# 05_Button.net
KiCad netlist of a schematic drawn in Altium Designer
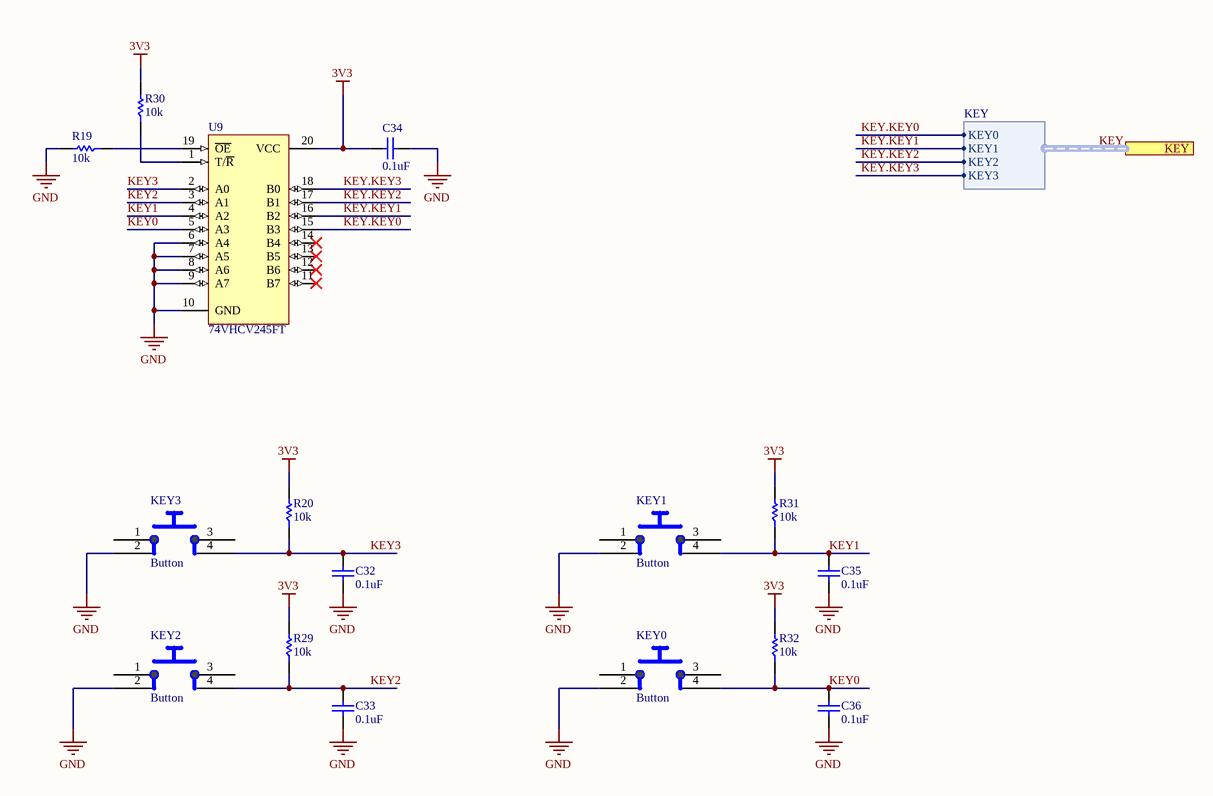
[diagram p0: 05_Button.SchDoc]

(export (version "E")
  (design (tool "Eeschema 10.0.6"))
  (components
    (comp (ref "C32")
      (value "0.1uF")
      (footprint "CAP0603R")
      (description "Capacitor")
      (libsource (lib "Quatro_SchLib") (part "C"))
    )
    (comp (ref "C33")
      (value "0.1uF")
      (footprint "CAP0603R")
      (description "Capacitor")
      (libsource (lib "Quatro_SchLib") (part "C"))
    )
    (comp (ref "C34")
      (value "0.1uF")
      (footprint "CAP0603R")
      (description "Capacitor")
      (libsource (lib "Quatro_SchLib") (part "C"))
    )
    (comp (ref "C35")
      (value "0.1uF")
      (footprint "CAP0603R")
      (description "Capacitor")
      (libsource (lib "Quatro_SchLib") (part "C"))
    )
    (comp (ref "C36")
      (value "0.1uF")
      (footprint "CAP0603R")
      (description "Capacitor")
      (libsource (lib "Quatro_SchLib") (part "C"))
    )
    (comp (ref "KEY0")
      (value "Button")
      (footprint "But_PTS645SMT")
      (libsource (lib "Quatro_SchLib") (part "BUT"))
    )
    (comp (ref "KEY1")
      (value "Button")
      (footprint "But_PTS645SMT")
      (libsource (lib "Quatro_SchLib") (part "BUT"))
    )
    (comp (ref "KEY2")
      (value "Button")
      (footprint "But_PTS645SMT")
      (libsource (lib "Quatro_SchLib") (part "BUT"))
    )
    (comp (ref "KEY3")
      (value "Button")
      (footprint "But_PTS645SMT")
      (libsource (lib "Quatro_SchLib") (part "BUT"))
    )
    (comp (ref "R19")
      (value "10k")
      (footprint "RES0603R")
      (description "Resistor")
      (libsource (lib "Quatro_SchLib") (part "R"))
    )
    (comp (ref "R20")
      (value "10k")
      (footprint "RES0603R")
      (description "Resistor")
      (libsource (lib "Quatro_SchLib") (part "R"))
    )
    (comp (ref "R29")
      (value "10k")
      (footprint "RES0603R")
      (description "Resistor")
      (libsource (lib "Quatro_SchLib") (part "R"))
    )
    (comp (ref "R30")
      (value "10k")
      (footprint "RES0603R")
      (description "Resistor")
      (libsource (lib "Quatro_SchLib") (part "R"))
    )
    (comp (ref "R31")
      (value "10k")
      (footprint "RES0603R")
      (description "Resistor")
      (libsource (lib "Quatro_SchLib") (part "R"))
    )
    (comp (ref "R32")
      (value "10k")
      (footprint "RES0603R")
      (description "Resistor")
      (libsource (lib "Quatro_SchLib") (part "R"))
    )
    (comp (ref "U9")
      (value "74VHCV245FT")
      (footprint "TSSOP20B")
      (description "Octal Schmitt Bus Transceiver with 3-State Outputs")
      (fields
        (field (name "01 CREATED BY") "Rodrigo Maureira @ 2018-04-05")
        (field (name "02 REVIEWED BY") "*")
      )
      (libsource (lib "Quatro_SchLib") (part "74VHCV245FT"))
    )
  )
  (nets
    (net (code "2") (name "/KEY.KEY0") (class "Default")
      (node (ref "U9") (pin "15") (pinfunction "B3_15") (pintype "bidirectional"))
    )
    (net (code "3") (name "/KEY.KEY1") (class "Default")
      (node (ref "U9") (pin "16") (pinfunction "B2_16") (pintype "bidirectional"))
    )
    (net (code "4") (name "/KEY.KEY2") (class "Default")
      (node (ref "U9") (pin "17") (pinfunction "B1_17") (pintype "bidirectional"))
    )
    (net (code "5") (name "/KEY.KEY3") (class "Default")
      (node (ref "U9") (pin "18") (pinfunction "B0_18") (pintype "bidirectional"))
    )
    (net (code "6") (name "/KEY0") (class "Default")
      (node (ref "C36") (pin "2") (pinfunction "2_2") (pintype "passive"))
      (node (ref "KEY0") (pin "4") (pinfunction "1_4") (pintype "passive"))
      (node (ref "R32") (pin "1") (pintype "passive"))
      (node (ref "U9") (pin "5") (pinfunction "A3_5") (pintype "bidirectional"))
    )
    (net (code "7") (name "/KEY1") (class "Default")
      (node (ref "C35") (pin "2") (pinfunction "2_2") (pintype "passive"))
      (node (ref "KEY1") (pin "4") (pinfunction "1_4") (pintype "passive"))
      (node (ref "R31") (pin "1") (pintype "passive"))
      (node (ref "U9") (pin "4") (pinfunction "A2_4") (pintype "bidirectional"))
    )
    (net (code "8") (name "/KEY2") (class "Default")
      (node (ref "C33") (pin "2") (pinfunction "2_2") (pintype "passive"))
      (node (ref "KEY2") (pin "4") (pinfunction "1_4") (pintype "passive"))
      (node (ref "R29") (pin "1") (pintype "passive"))
      (node (ref "U9") (pin "3") (pinfunction "A1_3") (pintype "bidirectional"))
    )
    (net (code "9") (name "/KEY3") (class "Default")
      (node (ref "C32") (pin "2") (pinfunction "2_2") (pintype "passive"))
      (node (ref "KEY3") (pin "4") (pinfunction "1_4") (pintype "passive"))
      (node (ref "R20") (pin "1") (pintype "passive"))
      (node (ref "U9") (pin "2") (pinfunction "A0_2") (pintype "bidirectional"))
    )
    (net (code "11") (name "3V3") (class "Default")
      (node (ref "C34") (pin "1") (pinfunction "1_1") (pintype "passive"))
      (node (ref "R20") (pin "2") (pintype "passive"))
      (node (ref "R29") (pin "2") (pintype "passive"))
      (node (ref "R30") (pin "2") (pintype "passive"))
      (node (ref "R31") (pin "2") (pintype "passive"))
      (node (ref "R32") (pin "2") (pintype "passive"))
      (node (ref "U9") (pin "20") (pinfunction "VCC_20") (pintype "power_in"))
    )
    (net (code "12") (name "GND") (class "Default")
      (node (ref "C32") (pin "1") (pinfunction "1_1") (pintype "passive"))
      (node (ref "C33") (pin "1") (pinfunction "1_1") (pintype "passive"))
      (node (ref "C34") (pin "2") (pinfunction "2_2") (pintype "passive"))
      (node (ref "C35") (pin "1") (pinfunction "1_1") (pintype "passive"))
      (node (ref "C36") (pin "1") (pinfunction "1_1") (pintype "passive"))
      (node (ref "KEY0") (pin "2") (pinfunction "2_2") (pintype "passive"))
      (node (ref "KEY1") (pin "2") (pinfunction "2_2") (pintype "passive"))
      (node (ref "KEY2") (pin "2") (pinfunction "2_2") (pintype "passive"))
      (node (ref "KEY3") (pin "2") (pinfunction "2_2") (pintype "passive"))
      (node (ref "R19") (pin "2") (pintype "passive"))
      (node (ref "U9") (pin "10") (pinfunction "GND_10") (pintype "power_in"))
      (node (ref "U9") (pin "6") (pinfunction "A4_6") (pintype "bidirectional"))
      (node (ref "U9") (pin "7") (pinfunction "A5_7") (pintype "bidirectional"))
      (node (ref "U9") (pin "8") (pinfunction "A6_8") (pintype "bidirectional"))
      (node (ref "U9") (pin "9") (pinfunction "A7_9") (pintype "bidirectional"))
    )
    (net (code "13") (name "Net-(U9-T{slash}~{R})") (class "Default")
      (node (ref "R30") (pin "1") (pintype "passive"))
      (node (ref "U9") (pin "1") (pinfunction "T/~{R}_1") (pintype "input"))
    )
    (net (code "14") (name "Net-(U9-~{OE})") (class "Default")
      (node (ref "R19") (pin "1") (pintype "passive"))
      (node (ref "U9") (pin "19") (pinfunction "~{OE}_19") (pintype "input"))
    )
    (net (code "15") (name "unconnected-(KEY0-29-Pad1)") (class "Default")
      (node (ref "KEY0") (pin "1") (pinfunction "29_1") (pintype "passive"))
    )
    (net (code "16") (name "unconnected-(KEY0-29-Pad3)") (class "Default")
      (node (ref "KEY0") (pin "3") (pinfunction "29_3") (pintype "passive"))
    )
    (net (code "17") (name "unconnected-(KEY1-29-Pad1)") (class "Default")
      (node (ref "KEY1") (pin "1") (pinfunction "29_1") (pintype "passive"))
    )
    (net (code "18") (name "unconnected-(KEY1-29-Pad3)") (class "Default")
      (node (ref "KEY1") (pin "3") (pinfunction "29_3") (pintype "passive"))
    )
    (net (code "19") (name "unconnected-(KEY2-29-Pad1)") (class "Default")
      (node (ref "KEY2") (pin "1") (pinfunction "29_1") (pintype "passive"))
    )
    (net (code "20") (name "unconnected-(KEY2-29-Pad3)") (class "Default")
      (node (ref "KEY2") (pin "3") (pinfunction "29_3") (pintype "passive"))
    )
    (net (code "21") (name "unconnected-(KEY3-29-Pad1)") (class "Default")
      (node (ref "KEY3") (pin "1") (pinfunction "29_1") (pintype "passive"))
    )
    (net (code "22") (name "unconnected-(KEY3-29-Pad3)") (class "Default")
      (node (ref "KEY3") (pin "3") (pinfunction "29_3") (pintype "passive"))
    )
    (net (code "23") (name "unconnected-(U9-B4-Pad14)") (class "Default")
      (node (ref "U9") (pin "14") (pinfunction "B4_14") (pintype "bidirectional+no_connect"))
    )
    (net (code "24") (name "unconnected-(U9-B5-Pad13)") (class "Default")
      (node (ref "U9") (pin "13") (pinfunction "B5_13") (pintype "bidirectional+no_connect"))
    )
    (net (code "25") (name "unconnected-(U9-B6-Pad12)") (class "Default")
      (node (ref "U9") (pin "12") (pinfunction "B6_12") (pintype "bidirectional+no_connect"))
    )
    (net (code "26") (name "unconnected-(U9-B7-Pad11)") (class "Default")
      (node (ref "U9") (pin "11") (pinfunction "B7_11") (pintype "bidirectional+no_connect"))
    )
  )
)
